# untitled.net
KiCad netlist of a schematic drawn in EAGLE
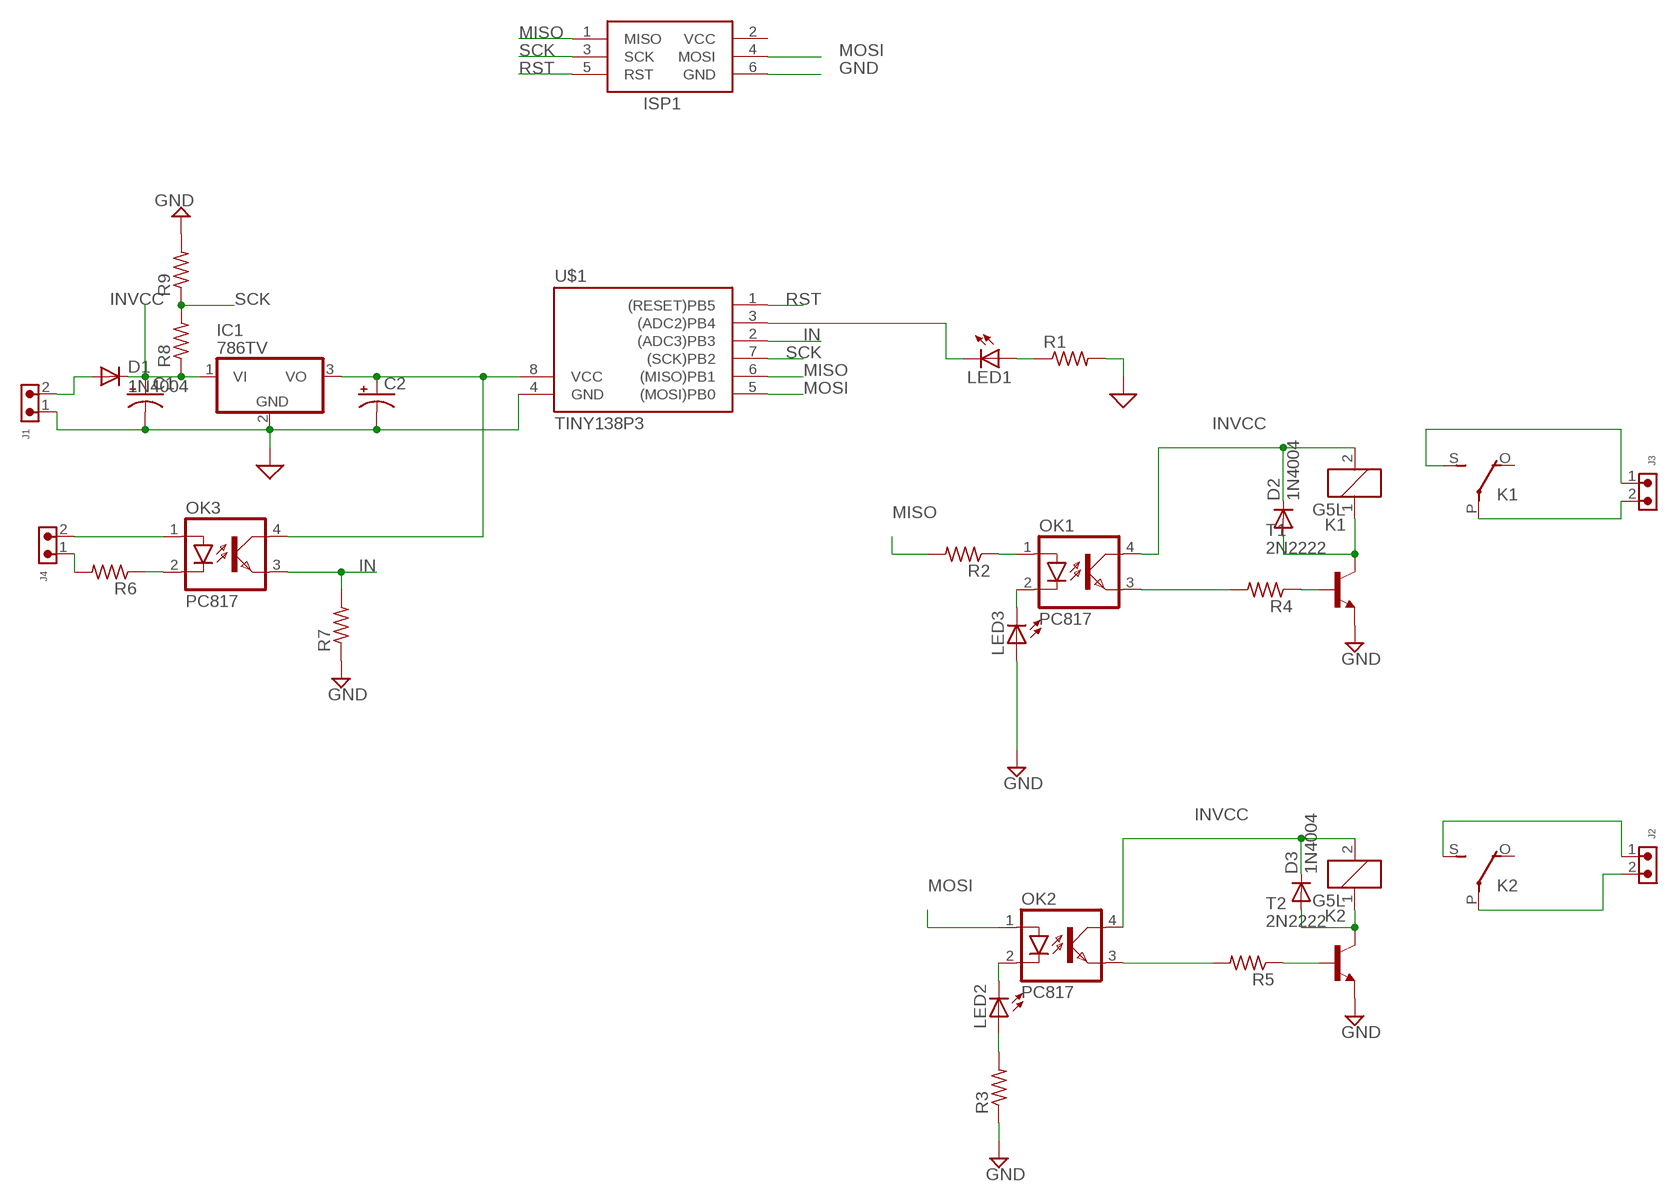
[diagram p0: schematic, sheet 1]

(export (version "E")
  (design (tool "Eeschema 10.0.6"))
  (components
    (comp (ref "C1")
      (value "CAPACITOR-PE7.5-16")
      (footprint "eagle-import:E7,5-16")
      (libsource (lib "eagle-import") (part "CAPACITOR-PE7.5-16"))
    )
    (comp (ref "C2")
      (value "CAPACITOR-PE2,5-6E")
      (footprint "eagle-import:E2,5-6E")
      (libsource (lib "eagle-import") (part "CAPACITOR-PE2,5-6E"))
    )
    (comp (ref "D1")
      (value "1N4004")
      (footprint "eagle-import:DO41-10")
      (libsource (lib "eagle-import") (part "1N4004"))
    )
    (comp (ref "D2")
      (value "1N4004")
      (footprint "eagle-import:DO41-10")
      (libsource (lib "eagle-import") (part "1N4004"))
    )
    (comp (ref "D3")
      (value "1N4004")
      (footprint "eagle-import:DO41-10")
      (libsource (lib "eagle-import") (part "1N4004"))
    )
    (comp (ref "IC1")
      (value "786TV")
      (footprint "eagle-import:TO220V")
      (libsource (lib "eagle-import") (part "78TV6"))
    )
    (comp (ref "ISP1")
      (value "AVRISP-6")
      (footprint "eagle-import:AVRISP")
      (libsource (lib "eagle-import") (part "AVRISP-6"))
    )
    (comp (ref "J1")
      (value "691305530002")
      (footprint "eagle-import:691305530002")
      (libsource (lib "eagle-import") (part "691305530002"))
    )
    (comp (ref "J2")
      (value "691305530002")
      (footprint "eagle-import:691305530002")
      (libsource (lib "eagle-import") (part "691305530002"))
    )
    (comp (ref "J3")
      (value "691305530002")
      (footprint "eagle-import:691305530002")
      (libsource (lib "eagle-import") (part "691305530002"))
    )
    (comp (ref "J4")
      (value "691305530002")
      (footprint "eagle-import:691305530002")
      (libsource (lib "eagle-import") (part "691305530002"))
    )
    (comp (ref "K1")
      (value "G5L")
      (footprint "eagle-import:G5LE")
      (libsource (lib "eagle-import") (part "G5L"))
    )
    (comp (ref "K2")
      (value "G5L")
      (footprint "eagle-import:G5LE")
      (libsource (lib "eagle-import") (part "G5L"))
    )
    (comp (ref "LED1")
      (value "LED5MM")
      (footprint "eagle-import:LED5MM")
      (libsource (lib "eagle-import") (part "LED5MM"))
    )
    (comp (ref "LED2")
      (value "LED5MM")
      (footprint "eagle-import:LED5MM")
      (libsource (lib "eagle-import") (part "LED5MM"))
    )
    (comp (ref "LED3")
      (value "LED5MM")
      (footprint "eagle-import:LED5MM")
      (libsource (lib "eagle-import") (part "LED5MM"))
    )
    (comp (ref "OK1")
      (value "PC817")
      (footprint "eagle-import:DIL04")
      (fields (field (name "MPN") "PC817X4J000F"))
      (libsource (lib "eagle-import") (part "PC817"))
    )
    (comp (ref "OK2")
      (value "PC817")
      (footprint "eagle-import:DIL04")
      (fields (field (name "MPN") "PC817X4J000F"))
      (libsource (lib "eagle-import") (part "PC817"))
    )
    (comp (ref "OK3")
      (value "PC817")
      (footprint "eagle-import:DIL04")
      (fields (field (name "MPN") "PC817X4J000F"))
      (libsource (lib "eagle-import") (part "PC817"))
    )
    (comp (ref "R1")
      (value "R-US_0207/15")
      (footprint "eagle-import:0207_15")
      (libsource (lib "eagle-import") (part "adafruit_420_R-US_0207/15"))
    )
    (comp (ref "R2")
      (value "R-US_0207/7")
      (footprint "eagle-import:0207_7")
      (libsource (lib "eagle-import") (part "R-US_0207/7"))
    )
    (comp (ref "R3")
      (value "R-US_0207/7")
      (footprint "eagle-import:0207_7")
      (libsource (lib "eagle-import") (part "adafruit_420_R-US_0207/7"))
    )
    (comp (ref "R4")
      (value "R-US_0207/9")
      (footprint "eagle-import:0207_9")
      (libsource (lib "eagle-import") (part "R-US_0207/9"))
    )
    (comp (ref "R5")
      (value "R-US_0207/9")
      (footprint "eagle-import:0207_9")
      (libsource (lib "eagle-import") (part "R-US_0207/9"))
    )
    (comp (ref "R6")
      (value "R-US_0207/7")
      (footprint "eagle-import:0207_7")
      (libsource (lib "eagle-import") (part "R-US_0207/7"))
    )
    (comp (ref "R7")
      (value "R-US_0207/12")
      (footprint "eagle-import:0207_12")
      (libsource (lib "eagle-import") (part "adafruit_420_R-US_0207/12"))
    )
    (comp (ref "R8")
      (value "R-US_0207/7")
      (footprint "eagle-import:0207_7")
      (libsource (lib "eagle-import") (part "R-US_0207/7"))
    )
    (comp (ref "R9")
      (value "R-US_0207/7")
      (footprint "eagle-import:0207_7")
      (libsource (lib "eagle-import") (part "R-US_0207/7"))
    )
    (comp (ref "T1")
      (value "2N2222")
      (footprint "eagle-import:TO92-EBC-OVAL")
      (libsource (lib "eagle-import") (part "2N2222"))
    )
    (comp (ref "T2")
      (value "2N2222")
      (footprint "eagle-import:TO92-EBC-OVAL")
      (libsource (lib "eagle-import") (part "2N2222"))
    )
    (comp (ref "U$1")
      (value "TINY138P3")
      (footprint "eagle-import:DIL08")
      (libsource (lib "eagle-import") (part "TINY138P3"))
    )
  )
  (nets
    (net (code "1") (name "/IN") (class "Default")
      (node (ref "OK3") (pin "3") (pinfunction "EMIT_3") (pintype "passive"))
      (node (ref "R7") (pin "2") (pinfunction "2_2") (pintype "passive"))
      (node (ref "U$1") (pin "2") (pinfunction "(ADC3)PB3_2") (pintype "bidirectional"))
    )
    (net (code "2") (name "/INVCC") (class "Default")
      (node (ref "C1") (pin "+") (pinfunction "+_+") (pintype "passive"))
      (node (ref "D1") (pin "C") (pinfunction "C_C") (pintype "passive"))
      (node (ref "D2") (pin "C") (pinfunction "C_C") (pintype "passive"))
      (node (ref "D3") (pin "C") (pinfunction "C_C") (pintype "passive"))
      (node (ref "IC1") (pin "1") (pinfunction "VI_1") (pintype "input"))
      (node (ref "K1") (pin "2") (pinfunction "2_2") (pintype "passive"))
      (node (ref "K2") (pin "2") (pinfunction "2_2") (pintype "passive"))
      (node (ref "OK1") (pin "4") (pinfunction "COL_4") (pintype "passive"))
      (node (ref "OK2") (pin "4") (pinfunction "COL_4") (pintype "passive"))
      (node (ref "R8") (pin "1") (pinfunction "1_1") (pintype "passive"))
    )
    (net (code "3") (name "/MISO") (class "Default")
      (node (ref "ISP1") (pin "1") (pinfunction "MISO_1") (pintype "input"))
      (node (ref "R2") (pin "2") (pinfunction "2_2") (pintype "passive"))
      (node (ref "U$1") (pin "6") (pinfunction "(MISO)PB1_6") (pintype "bidirectional"))
    )
    (net (code "4") (name "/MOSI") (class "Default")
      (node (ref "ISP1") (pin "4") (pinfunction "MOSI_4") (pintype "output"))
      (node (ref "OK2") (pin "1") (pinfunction "A_1") (pintype "passive"))
      (node (ref "U$1") (pin "5") (pinfunction "(MOSI)PB0_5") (pintype "bidirectional"))
    )
    (net (code "5") (name "/RST") (class "Default")
      (node (ref "ISP1") (pin "5") (pinfunction "RST_5") (pintype "output"))
      (node (ref "U$1") (pin "1") (pinfunction "(RESET)PB5_1") (pintype "bidirectional"))
    )
    (net (code "6") (name "/SCK") (class "Default")
      (node (ref "ISP1") (pin "3") (pinfunction "SCK_3") (pintype "output"))
      (node (ref "R8") (pin "2") (pinfunction "2_2") (pintype "passive"))
      (node (ref "R9") (pin "1") (pinfunction "1_1") (pintype "passive"))
      (node (ref "U$1") (pin "7") (pinfunction "(SCK)PB2_7") (pintype "bidirectional"))
    )
    (net (code "7") (name "/VCC") (class "Default")
      (node (ref "ISP1") (pin "2") (pinfunction "VCC_2") (pintype "power_in"))
    )
    (net (code "8") (name "GND") (class "Default")
      (node (ref "C1") (pin "-") (pinfunction "-_-") (pintype "passive"))
      (node (ref "C2") (pin "-") (pinfunction "-_-") (pintype "passive"))
      (node (ref "IC1") (pin "2") (pinfunction "GND_2") (pintype "passive"))
      (node (ref "ISP1") (pin "6") (pinfunction "GND_6") (pintype "power_in"))
      (node (ref "J1") (pin "1") (pinfunction "1_1") (pintype "passive"))
      (node (ref "LED3") (pin "A") (pinfunction "A_A") (pintype "passive"))
      (node (ref "R1") (pin "2") (pinfunction "2_2") (pintype "passive"))
      (node (ref "R3") (pin "1") (pinfunction "1_1") (pintype "passive"))
      (node (ref "R7") (pin "1") (pinfunction "1_1") (pintype "passive"))
      (node (ref "R9") (pin "2") (pinfunction "2_2") (pintype "passive"))
      (node (ref "T1") (pin "E") (pinfunction "E_E") (pintype "passive"))
      (node (ref "T2") (pin "E") (pinfunction "E_E") (pintype "passive"))
      (node (ref "U$1") (pin "4") (pinfunction "GND_4") (pintype "power_in"))
    )
    (net (code "9") (name "Net-(D1-PadA)") (class "Default")
      (node (ref "D1") (pin "A") (pinfunction "A_A") (pintype "passive"))
      (node (ref "J1") (pin "2") (pinfunction "2_2") (pintype "passive"))
    )
    (net (code "10") (name "Net-(D2-PadA)") (class "Default")
      (node (ref "D2") (pin "A") (pinfunction "A_A") (pintype "passive"))
      (node (ref "K1") (pin "1") (pinfunction "1_1") (pintype "passive"))
      (node (ref "T1") (pin "C") (pinfunction "C_C") (pintype "passive"))
    )
    (net (code "11") (name "Net-(D3-PadA)") (class "Default")
      (node (ref "D3") (pin "A") (pinfunction "A_A") (pintype "passive"))
      (node (ref "K2") (pin "1") (pinfunction "1_1") (pintype "passive"))
      (node (ref "T2") (pin "C") (pinfunction "C_C") (pintype "passive"))
    )
    (net (code "12") (name "Net-(IC1-VO)") (class "Default")
      (node (ref "C2") (pin "+") (pinfunction "+_+") (pintype "passive"))
      (node (ref "IC1") (pin "3") (pinfunction "VO_3") (pintype "passive"))
      (node (ref "OK3") (pin "4") (pinfunction "COL_4") (pintype "passive"))
      (node (ref "U$1") (pin "8") (pinfunction "VCC_8") (pintype "power_in"))
    )
    (net (code "13") (name "Net-(J2-Pad1)") (class "Default")
      (node (ref "J2") (pin "1") (pinfunction "1_1") (pintype "passive"))
      (node (ref "K2") (pin "S") (pinfunction "S_S") (pintype "passive"))
    )
    (net (code "14") (name "Net-(J2-Pad2)") (class "Default")
      (node (ref "J2") (pin "2") (pinfunction "2_2") (pintype "passive"))
      (node (ref "K2") (pin "P") (pinfunction "P_P") (pintype "passive"))
    )
    (net (code "15") (name "Net-(J3-Pad1)") (class "Default")
      (node (ref "J3") (pin "1") (pinfunction "1_1") (pintype "passive"))
      (node (ref "K1") (pin "S") (pinfunction "S_S") (pintype "passive"))
    )
    (net (code "16") (name "Net-(J3-Pad2)") (class "Default")
      (node (ref "J3") (pin "2") (pinfunction "2_2") (pintype "passive"))
      (node (ref "K1") (pin "P") (pinfunction "P_P") (pintype "passive"))
    )
    (net (code "17") (name "Net-(J4-Pad1)") (class "Default")
      (node (ref "J4") (pin "1") (pinfunction "1_1") (pintype "passive"))
      (node (ref "R6") (pin "2") (pinfunction "2_2") (pintype "passive"))
    )
    (net (code "18") (name "Net-(LED1-C)") (class "Default")
      (node (ref "LED1") (pin "K") (pinfunction "C_K") (pintype "passive"))
      (node (ref "U$1") (pin "3") (pinfunction "(ADC2)PB4_3") (pintype "bidirectional"))
    )
    (net (code "19") (name "Net-(LED1-PadA)") (class "Default")
      (node (ref "LED1") (pin "A") (pinfunction "A_A") (pintype "passive"))
      (node (ref "R1") (pin "1") (pinfunction "1_1") (pintype "passive"))
    )
    (net (code "20") (name "Net-(LED2-C)") (class "Default")
      (node (ref "LED2") (pin "K") (pinfunction "C_K") (pintype "passive"))
      (node (ref "OK2") (pin "2") (pinfunction "C_2") (pintype "passive"))
    )
    (net (code "21") (name "Net-(LED2-PadA)") (class "Default")
      (node (ref "LED2") (pin "A") (pinfunction "A_A") (pintype "passive"))
      (node (ref "R3") (pin "2") (pinfunction "2_2") (pintype "passive"))
    )
    (net (code "22") (name "Net-(LED3-C)") (class "Default")
      (node (ref "LED3") (pin "K") (pinfunction "C_K") (pintype "passive"))
      (node (ref "OK1") (pin "2") (pinfunction "C_2") (pintype "passive"))
    )
    (net (code "23") (name "Net-(OK1-A)") (class "Default")
      (node (ref "OK1") (pin "1") (pinfunction "A_1") (pintype "passive"))
      (node (ref "R2") (pin "1") (pinfunction "1_1") (pintype "passive"))
    )
    (net (code "24") (name "Net-(OK1-EMIT)") (class "Default")
      (node (ref "OK1") (pin "3") (pinfunction "EMIT_3") (pintype "passive"))
      (node (ref "R4") (pin "2") (pinfunction "2_2") (pintype "passive"))
    )
    (net (code "25") (name "Net-(OK2-EMIT)") (class "Default")
      (node (ref "OK2") (pin "3") (pinfunction "EMIT_3") (pintype "passive"))
      (node (ref "R5") (pin "2") (pinfunction "2_2") (pintype "passive"))
    )
    (net (code "26") (name "Net-(OK3-A)") (class "Default")
      (node (ref "J4") (pin "2") (pinfunction "2_2") (pintype "passive"))
      (node (ref "OK3") (pin "1") (pinfunction "A_1") (pintype "passive"))
    )
    (net (code "27") (name "Net-(OK3-C)") (class "Default")
      (node (ref "OK3") (pin "2") (pinfunction "C_2") (pintype "passive"))
      (node (ref "R6") (pin "1") (pinfunction "1_1") (pintype "passive"))
    )
    (net (code "28") (name "Net-(R4-Pad1)") (class "Default")
      (node (ref "R4") (pin "1") (pinfunction "1_1") (pintype "passive"))
      (node (ref "T1") (pin "B") (pinfunction "B_B") (pintype "passive"))
    )
    (net (code "29") (name "Net-(R5-Pad1)") (class "Default")
      (node (ref "R5") (pin "1") (pinfunction "1_1") (pintype "passive"))
      (node (ref "T2") (pin "B") (pinfunction "B_B") (pintype "passive"))
    )
    (net (code "30") (name "unconnected-(K1-PadO)") (class "Default")
      (node (ref "K1") (pin "O") (pinfunction "O_O") (pintype "passive"))
    )
    (net (code "31") (name "unconnected-(K2-PadO)") (class "Default")
      (node (ref "K2") (pin "O") (pinfunction "O_O") (pintype "passive"))
    )
  )
)
